# RS485.net
KiCad netlist of a schematic drawn in Altium Designer
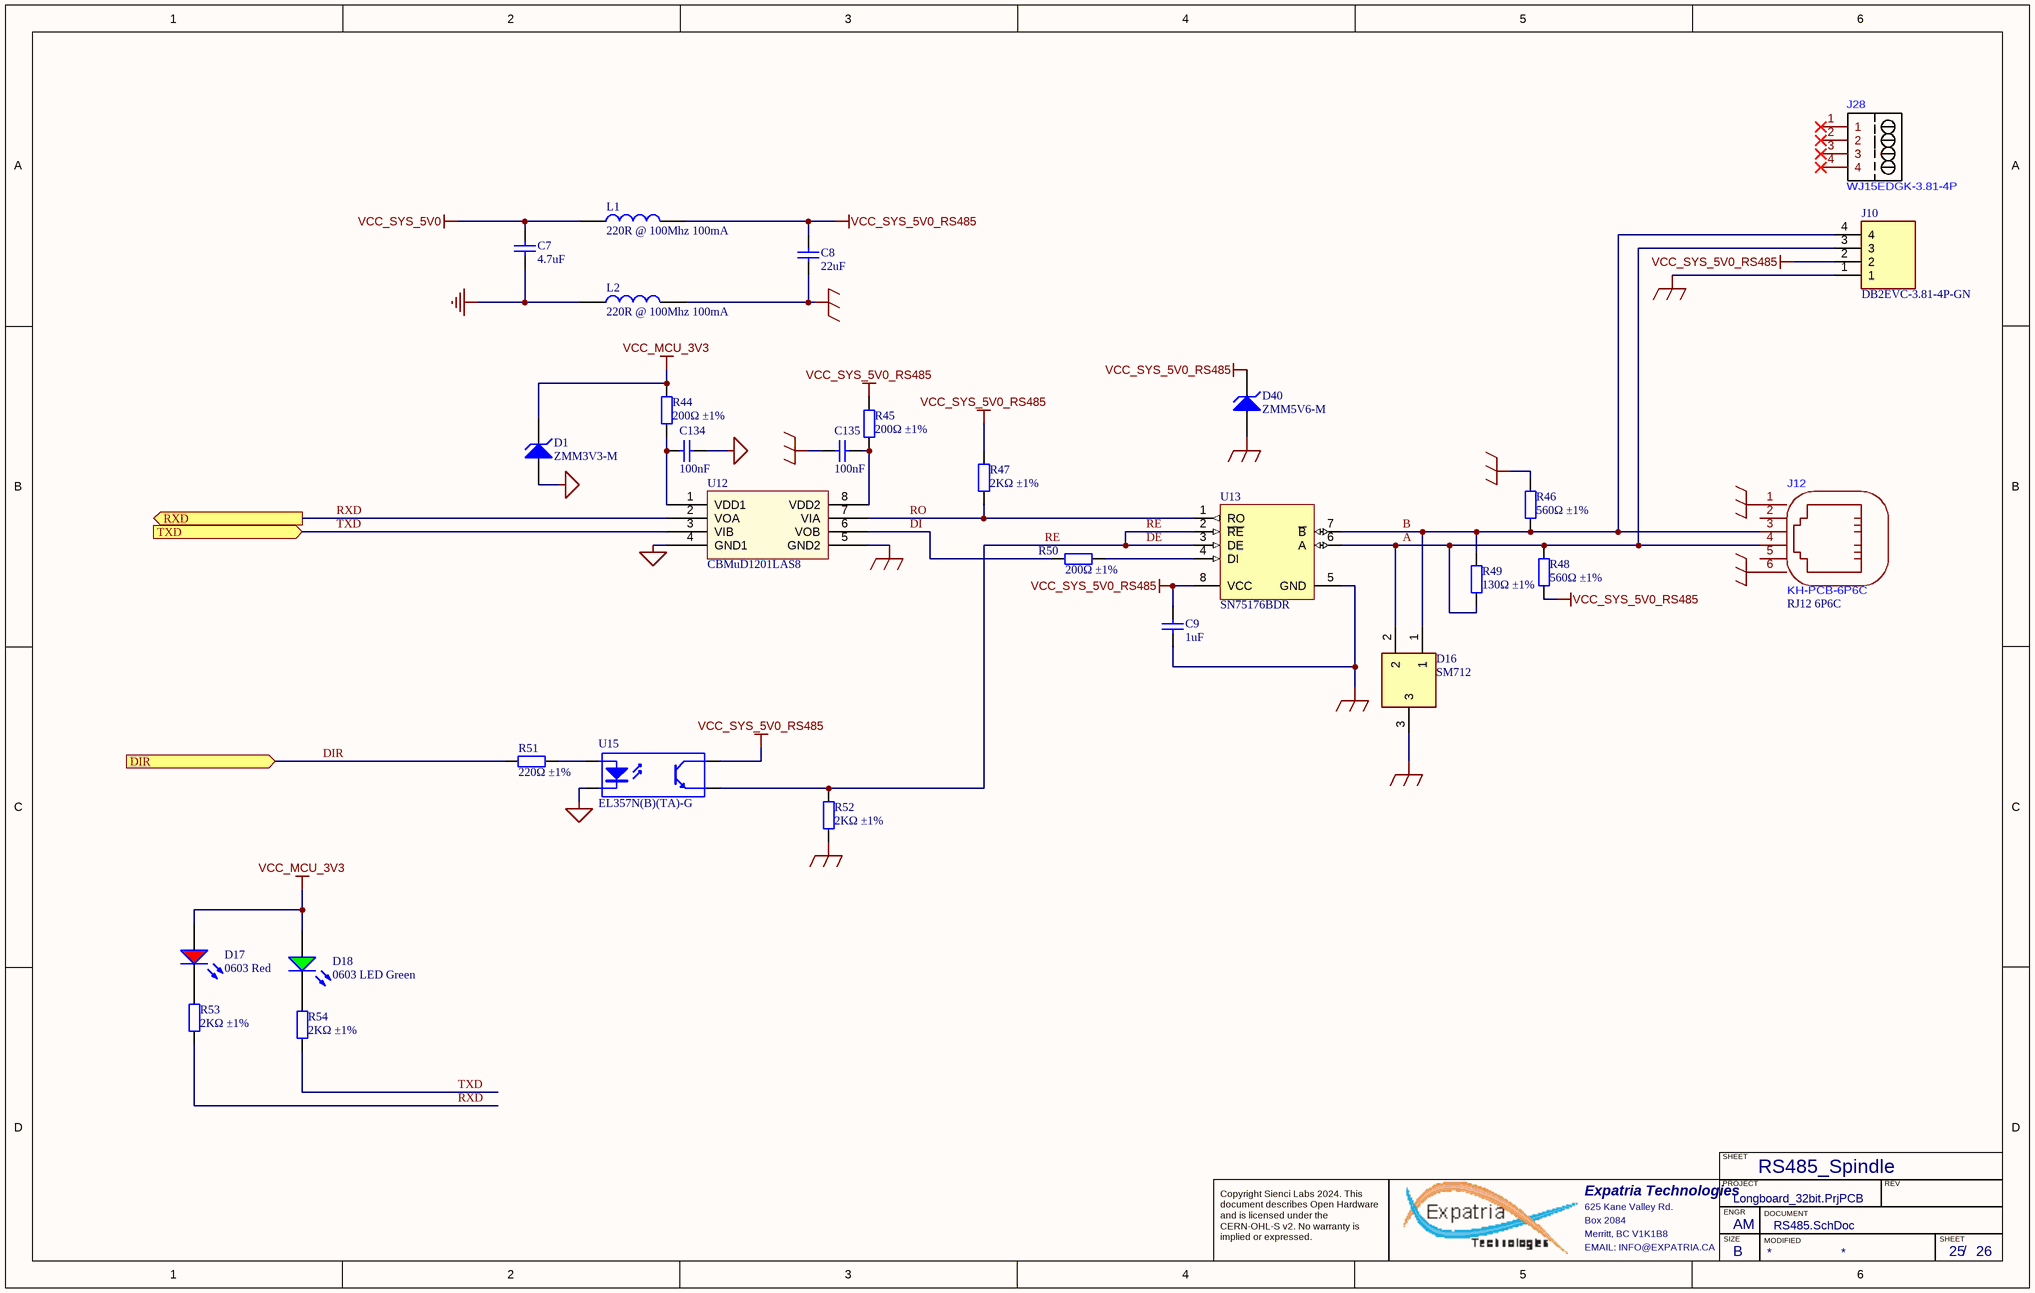
[diagram p0: RS485.SchDoc]

(export (version "E")
  (design (tool "Eeschema 10.0.6"))
  (components
    (comp (ref "C7")
      (value "4.7uF")
      (footprint "0805_C")
      (description "Chip capacitors")
      (fields
        (field (name "MANUFACTURER") "Samsung Electro-Mechanics")
        (field (name "MANUFACTURER PART NUMBER") "CL21A475KAQNNNE")
      )
      (libsource (lib "Cap") (part "0805 4.7uF (475) 10% 25V"))
    )
    (comp (ref "C8")
      (value "22uF")
      (footprint "0805_C")
      (description "25V 22uF X5R ±20% 0805 Multilayer Ceramic Capacitors MLCC - SMD/SMT ROHS")
      (fields (field (name "MANUFACTURER") "Samsung Electro-Mechanics") (field (name "TOLERANCE") "20%"))
      (libsource (lib "Sienci_Labs") (part "0805 22uF (226) 20% 25V"))
    )
    (comp (ref "C9")
      (value "1uF")
      (footprint "0603_C")
      (description "Chip capacitors")
      (fields
        (field (name "MANUFACTURER") "Samsung Electro-Mechanics")
        (field (name "MANUFACTURER PART NUMBER") "CL10A105KB8NNNC")
      )
      (libsource (lib "Cap") (part "0603 1uF (105) 10% 50V"))
    )
    (comp (ref "C134")
      (value "100nF")
      (footprint "0402_C")
      (description "16V 100nF X7R ±10% 0402 Multilayer Ceramic Capacitors MLCC - SMD/SMT ROHS")
      (fields (field (name "MANUFACTURER") "Samsung Electro-Mechanics") (field (name "TOLERANCE") "10%"))
      (libsource (lib "Sienci_Labs") (part "0402 100nF (104) 10% 16V"))
    )
    (comp (ref "C135")
      (value "100nF")
      (footprint "0402_C")
      (description "16V 100nF X7R ±10% 0402 Multilayer Ceramic Capacitors MLCC - SMD/SMT ROHS")
      (fields (field (name "MANUFACTURER") "Samsung Electro-Mechanics") (field (name "TOLERANCE") "10%"))
      (libsource (lib "Sienci_Labs") (part "0402 100nF (104) 10% 16V"))
    )
    (comp (ref "D1")
      (value "ZMM3V3-M")
      (footprint "LL-34")
      (description "Single 3.1V~3.5V 500mW 3.3V LL-34 Zener Diodes ROHS")
      (fields (field (name "MANUFACTURER") "ST(Semtech)"))
      (libsource (lib "Sienci_Labs") (part "LL-34 ZMM3V3-M"))
    )
    (comp (ref "D16")
      (value "SM712")
      (footprint "SOT95P230X117-3N")
      (description "Bidirectional 12V (Max), 7V (Max) 7.5V / 13.3V 10V / 20V 12A(8/20us) SOT-23-3 TVS RoHS")
      (fields (field (name "MANUFACTURER") "DOWO"))
      (libsource (lib "Sienci_Labs") (part "CDSOT23-SM712"))
    )
    (comp (ref "D17")
      (value "0603 Red")
      (footprint "0603_LED_S1")
      (fields
        (field (name "MANUFACTURER") "Everlight Elec")
        (field (name "MANUFACTURER PART NUMBER") "19-213SURC/S530-A3/TR8")
      )
      (libsource (lib "Sienci_Labs") (part "19-213SURC/S530-A3/TR8"))
    )
    (comp (ref "D18")
      (value "0603 LED Green")
      (footprint "0603_LED_S1 - GREEN")
      (fields
        (field (name "MANUFACTURER PART NUMBER") "19-217/GHC-YR1S2/3T")
        (field (name "MANUFACTURER") "Everlight Elec")
      )
      (libsource (lib "Sienci_Labs") (part "19-217/GHC-YR1S2/3T"))
    )
    (comp (ref "D40")
      (value "ZMM5V6-M")
      (footprint "LL-34")
      (description "Single 5.2V~6V 500mW 5.6V LL-34 Zener Diodes ROHS")
      (fields (field (name "MANUFACTURER") "ST(Semtech)"))
      (libsource (lib "Sienci_Labs") (part "LL-34 ZMM5V6-M"))
    )
    (comp (ref "J10")
      (value "DB2EVC-3.81-4P-GN")
      (footprint "CONN-TH_5P-P3.81_DB2EVC-3.81-4p")
      (description "3.81mm Green Board Edge/Receptacle-Close Push-Pull,P=3.81mm Pluggable System Terminal Block ROHS")
      (fields (field (name "MANUFACTURER") "DIBO"))
      (libsource (lib "Sienci_Labs") (part "DB2EVC-3.81-4P-GN"))
    )
    (comp (ref "J12")
      (value "KH-PCB-6P6C")
      (footprint "RJ11-TH_DS1133-S60BPX")
      (fields
        (field (name "MANUFACTURER") "Shenzhen Kinghelm Elec")
        (field (name "ALTIUM_VALUE") "RJ12 6P6C")
      )
      (libsource (lib "Sienci_Labs") (part "KH-PCB-6P6C"))
    )
    (comp (ref "J28")
      (value "WJ15EDGK-3.81-4P")
      (description "3.81mm Green Plug P=3.81mm Pluggable System Terminal Block ROHS")
      (fields (field (name "MANUFACTURER") "Ningbo"))
      (libsource (lib "Sienci_Labs") (part "WJ15EDGK-3.81-4P"))
    )
    (comp (ref "L1")
      (value "220R @ 100Mhz 100mA")
      (footprint "0402_L")
      (description "700mΩ ±25% 220Ω@100MHz 0402 Ferrite Beads ROHS")
      (fields
        (field (name "MANUFACTURER PART NUMBER") "CBG100505U221T")
        (field (name "MANUFACTURER") "FH (Guangdong Fenghua Advanced Tech)")
      )
      (libsource (lib "Sienci_Labs") (part "0402 220R@100Mhz 0.1A"))
    )
    (comp (ref "L2")
      (value "220R @ 100Mhz 100mA")
      (footprint "0402_L")
      (description "700mΩ ±25% 220Ω@100MHz 0402 Ferrite Beads ROHS")
      (fields
        (field (name "MANUFACTURER PART NUMBER") "CBG100505U221T")
        (field (name "MANUFACTURER") "FH (Guangdong Fenghua Advanced Tech)")
      )
      (libsource (lib "Sienci_Labs") (part "0402 220R@100Mhz 0.1A"))
    )
    (comp (ref "R44")
      (value "200Ω ±1%")
      (footprint "0402_R")
      (description "Chip resistor")
      (fields
        (field (name "MANUFACTURER") "Uniroyal Elec")
        (field (name "MANUFACTURER PART NUMBER") "0402WGF2000TCE")
      )
      (libsource (lib "RES") (part "0402 200R (2000) 1%"))
    )
    (comp (ref "R45")
      (value "200Ω ±1%")
      (footprint "0402_R")
      (description "Chip resistor")
      (fields
        (field (name "MANUFACTURER") "Uniroyal Elec")
        (field (name "MANUFACTURER PART NUMBER") "0402WGF2000TCE")
      )
      (libsource (lib "RES") (part "0402 200R (2000) 1%"))
    )
    (comp (ref "R46")
      (value "560Ω ±1%")
      (footprint "0603_R")
      (description "Chip resistor")
      (fields
        (field (name "MANUFACTURER") "Uniroyal Elec")
        (field (name "MANUFACTURER PART NUMBER") "0603WAF5600T5E")
      )
      (libsource (lib "RES") (part "0603 560R (5600) 1%"))
    )
    (comp (ref "R47")
      (value "2KΩ ±1%")
      (footprint "0603_R")
      (description "Chip resistor")
      (fields
        (field (name "MANUFACTURER") "Uniroyal Elec")
        (field (name "MANUFACTURER PART NUMBER") "0603WAF2001T5E")
      )
      (libsource (lib "RES") (part "0603 2K (2001) 1%"))
    )
    (comp (ref "R48")
      (value "560Ω ±1%")
      (footprint "0603_R")
      (description "Chip resistor")
      (fields
        (field (name "MANUFACTURER") "Uniroyal Elec")
        (field (name "MANUFACTURER PART NUMBER") "0603WAF5600T5E")
      )
      (libsource (lib "RES") (part "0603 560R (5600) 1%"))
    )
    (comp (ref "R49")
      (value "130Ω ±1%")
      (footprint "0603_R")
      (description "Chip resistor")
      (fields
        (field (name "MANUFACTURER") "Uniroyal Elec")
        (field (name "MANUFACTURER PART NUMBER") "0603WAF1300T5E")
      )
      (libsource (lib "RES") (part "0603 130R (1300) 1%"))
    )
    (comp (ref "R50")
      (value "200Ω ±1%")
      (footprint "0402_R")
      (description "Chip resistor")
      (fields
        (field (name "MANUFACTURER") "Uniroyal Elec")
        (field (name "MANUFACTURER PART NUMBER") "0402WGF2000TCE")
      )
      (libsource (lib "") (part "0402 200R (2000) 1%_1"))
    )
    (comp (ref "R51")
      (value "220Ω ±1%")
      (footprint "0402_R")
      (description "Chip resistor")
      (fields
        (field (name "MANUFACTURER") "Uniroyal Elec")
        (field (name "MANUFACTURER PART NUMBER") "0402WGF2200TCE")
      )
      (libsource (lib "RES") (part "0402 220R (2200) 1%"))
    )
    (comp (ref "R52")
      (value "2KΩ ±1%")
      (footprint "0603_R")
      (description "Chip resistor")
      (fields
        (field (name "MANUFACTURER") "Uniroyal Elec")
        (field (name "MANUFACTURER PART NUMBER") "0603WAF2001T5E")
      )
      (libsource (lib "RES") (part "0603 2K (2001) 1%"))
    )
    (comp (ref "R53")
      (value "2KΩ ±1%")
      (footprint "0603_R")
      (description "Chip resistor")
      (fields
        (field (name "MANUFACTURER") "Uniroyal Elec")
        (field (name "MANUFACTURER PART NUMBER") "0603WAF2001T5E")
      )
      (libsource (lib "RES") (part "0603 2K (2001) 1%"))
    )
    (comp (ref "R54")
      (value "2KΩ ±1%")
      (footprint "0603_R")
      (description "Chip resistor")
      (fields
        (field (name "MANUFACTURER") "Uniroyal Elec")
        (field (name "MANUFACTURER PART NUMBER") "0603WAF2001T5E")
      )
      (libsource (lib "RES") (part "0603 2K (2001) 1%"))
    )
    (comp (ref "U12")
      (value "CBMuD1201LAS8")
      (footprint "SOIC-8_150mil")
      (description "Dual Channel Isolator")
      (fields (field (name "MANUFACTURER") "Corebai Microelectronics"))
      (libsource (lib "Sienci_Labs") (part "CBMuD1201LAS8"))
    )
    (comp (ref "U13")
      (value "SN75176BDR")
      (footprint "SOIC-8_150mil")
      (description "RS-485/RS-422")
      (fields (field (name "MANUFACTURER") "Texas Instruments"))
      (libsource (lib "IC") (part "SN75176BDR_[C7063]"))
    )
    (comp (ref "U15")
      (value "EL357N(B)(TA)-G")
      (footprint "Miscellaneous Devices LC:SOP-4_P2.54")
      (description "80V 3750V 50mA 0.1V@1mA,20mA 1 6V 1.2V DC SOP-4-2.54mm Optocouplers - Phototransistor Output ROHS")
      (fields (field (name "MANUFACTURER") "Everlight Elec"))
      (libsource (lib "IC") (part "EL357N(B)(TA)-G_[C6649]"))
    )
  )
  (nets
    (net (code "1") (name "/A") (class "Default")
      (node (ref "D16") (pin "2") (pinfunction "2_2") (pintype "passive"))
      (node (ref "J10") (pin "3") (pinfunction "3_3") (pintype "passive"))
      (node (ref "J12") (pin "4") (pinfunction "PGD_4") (pintype "passive"))
      (node (ref "R48") (pin "1") (pinfunction "1_1") (pintype "passive"))
      (node (ref "R49") (pin "1") (pinfunction "1_1") (pintype "passive"))
      (node (ref "U13") (pin "6") (pinfunction "A_6") (pintype "bidirectional"))
    )
    (net (code "2") (name "/B") (class "Default")
      (node (ref "D16") (pin "1") (pinfunction "1_1") (pintype "passive"))
      (node (ref "J10") (pin "4") (pinfunction "4_4") (pintype "passive"))
      (node (ref "J12") (pin "3") (pinfunction "VSS_3") (pintype "passive"))
      (node (ref "R46") (pin "2") (pinfunction "2_2") (pintype "passive"))
      (node (ref "R49") (pin "2") (pinfunction "2_2") (pintype "passive"))
      (node (ref "U13") (pin "7") (pinfunction "~{B}_7") (pintype "bidirectional"))
    )
    (net (code "3") (name "/DE") (class "Default")
      (node (ref "R52") (pin "2") (pinfunction "2_2") (pintype "passive"))
      (node (ref "U13") (pin "2") (pinfunction "~{RE}_2") (pintype "input"))
      (node (ref "U13") (pin "3") (pinfunction "DE_3") (pintype "input"))
      (node (ref "U15") (pin "3") (pinfunction "E_3") (pintype "passive"))
    )
    (net (code "4") (name "/DI") (class "Default")
      (node (ref "R50") (pin "2") (pinfunction "2_2") (pintype "passive"))
      (node (ref "U12") (pin "6") (pinfunction "VOB_6") (pintype "passive"))
    )
    (net (code "5") (name "/DIR") (class "Default")
      (node (ref "R51") (pin "2") (pinfunction "2_2") (pintype "passive"))
    )
    (net (code "6") (name "/RO") (class "Default")
      (node (ref "R47") (pin "1") (pinfunction "1_1") (pintype "passive"))
      (node (ref "U12") (pin "7") (pinfunction "VIA_7") (pintype "passive"))
      (node (ref "U13") (pin "1") (pinfunction "RO_1") (pintype "output"))
    )
    (net (code "7") (name "/RXD") (class "Default")
      (node (ref "R53") (pin "1") (pinfunction "1_1") (pintype "passive"))
      (node (ref "U12") (pin "2") (pinfunction "VOA_2") (pintype "passive"))
    )
    (net (code "8") (name "/TXD") (class "Default")
      (node (ref "R54") (pin "1") (pinfunction "1_1") (pintype "passive"))
      (node (ref "U12") (pin "3") (pinfunction "VIB_3") (pintype "passive"))
    )
    (net (code "9") (name "GND") (class "Default")
      (node (ref "C7") (pin "1") (pinfunction "1_1") (pintype "passive"))
      (node (ref "L2") (pin "1") (pinfunction "1_1") (pintype "passive"))
    )
    (net (code "10") (name "MCU_GND") (class "Default")
      (node (ref "C134") (pin "2") (pinfunction "2_2") (pintype "passive"))
      (node (ref "D1") (pin "1") (pinfunction "A_1") (pintype "passive"))
      (node (ref "U12") (pin "4") (pinfunction "GND1_4") (pintype "passive"))
      (node (ref "U15") (pin "2") (pinfunction "K_2") (pintype "passive"))
    )
    (net (code "11") (name "MOD_GND") (class "Default")
      (node (ref "C135") (pin "1") (pinfunction "1_1") (pintype "passive"))
      (node (ref "C8") (pin "1") (pinfunction "1_1") (pintype "passive"))
      (node (ref "C9") (pin "1") (pinfunction "1_1") (pintype "passive"))
      (node (ref "D16") (pin "3") (pinfunction "3_3") (pintype "passive"))
      (node (ref "D40") (pin "1") (pinfunction "A_1") (pintype "passive"))
      (node (ref "J10") (pin "1") (pinfunction "1_1") (pintype "passive"))
      (node (ref "J12") (pin "1") (pinfunction "MCLR_1") (pintype "passive"))
      (node (ref "J12") (pin "6") (pinfunction "NC_6") (pintype "passive"))
      (node (ref "L2") (pin "2") (pinfunction "2_2") (pintype "passive"))
      (node (ref "R46") (pin "1") (pinfunction "1_1") (pintype "passive"))
      (node (ref "R52") (pin "1") (pinfunction "1_1") (pintype "passive"))
      (node (ref "U12") (pin "5") (pinfunction "GND2_5") (pintype "passive"))
      (node (ref "U13") (pin "5") (pinfunction "GND_5") (pintype "power_in"))
    )
    (net (code "12") (name "Net-(D17-PadK)") (class "Default")
      (node (ref "D17") (pin "K") (pinfunction "K_K") (pintype "passive"))
      (node (ref "R53") (pin "2") (pinfunction "2_2") (pintype "passive"))
    )
    (net (code "13") (name "Net-(D18-PadK)") (class "Default")
      (node (ref "D18") (pin "K") (pinfunction "K_K") (pintype "passive"))
      (node (ref "R54") (pin "2") (pinfunction "2_2") (pintype "passive"))
    )
    (net (code "14") (name "Net-(U12-VDD1)") (class "Default")
      (node (ref "C134") (pin "1") (pinfunction "1_1") (pintype "passive"))
      (node (ref "R44") (pin "1") (pinfunction "1_1") (pintype "passive"))
      (node (ref "U12") (pin "1") (pinfunction "VDD1_1") (pintype "passive"))
    )
    (net (code "15") (name "Net-(U12-VDD2)") (class "Default")
      (node (ref "C135") (pin "2") (pinfunction "2_2") (pintype "passive"))
      (node (ref "R45") (pin "1") (pinfunction "1_1") (pintype "passive"))
      (node (ref "U12") (pin "8") (pinfunction "VDD2_8") (pintype "passive"))
    )
    (net (code "16") (name "Net-(U13-DI)") (class "Default")
      (node (ref "R50") (pin "1") (pinfunction "1_1") (pintype "passive"))
      (node (ref "U13") (pin "4") (pinfunction "DI_4") (pintype "input"))
    )
    (net (code "17") (name "Net-(U15-A)") (class "Default")
      (node (ref "R51") (pin "1") (pinfunction "1_1") (pintype "passive"))
      (node (ref "U15") (pin "1") (pinfunction "A_1") (pintype "passive"))
    )
    (net (code "18") (name "VCC_MCU_3V3") (class "Default")
      (node (ref "D1") (pin "2") (pinfunction "K_2") (pintype "passive"))
      (node (ref "D17") (pin "A") (pinfunction "A_A") (pintype "passive"))
      (node (ref "D18") (pin "A") (pinfunction "A_A") (pintype "passive"))
      (node (ref "R44") (pin "2") (pinfunction "2_2") (pintype "passive"))
    )
    (net (code "19") (name "VCC_SYS_5V0") (class "Default")
      (node (ref "C7") (pin "2") (pinfunction "2_2") (pintype "passive"))
      (node (ref "L1") (pin "1") (pinfunction "1_1") (pintype "passive"))
    )
    (net (code "20") (name "VCC_SYS_5V0_RS485") (class "Default")
      (node (ref "C8") (pin "2") (pinfunction "2_2") (pintype "passive"))
      (node (ref "C9") (pin "2") (pinfunction "2_2") (pintype "passive"))
      (node (ref "D40") (pin "2") (pinfunction "K_2") (pintype "passive"))
      (node (ref "J10") (pin "2") (pinfunction "2_2") (pintype "passive"))
      (node (ref "L1") (pin "2") (pinfunction "2_2") (pintype "passive"))
      (node (ref "R45") (pin "2") (pinfunction "2_2") (pintype "passive"))
      (node (ref "R47") (pin "2") (pinfunction "2_2") (pintype "passive"))
      (node (ref "R48") (pin "2") (pinfunction "2_2") (pintype "passive"))
      (node (ref "U13") (pin "8") (pinfunction "VCC_8") (pintype "power_in"))
      (node (ref "U15") (pin "4") (pinfunction "C_4") (pintype "passive"))
    )
    (net (code "21") (name "unconnected-(J12-PGC-Pad5)") (class "Default")
      (node (ref "J12") (pin "5") (pinfunction "PGC_5") (pintype "passive"))
    )
    (net (code "22") (name "unconnected-(J12-VDD-Pad2)") (class "Default")
      (node (ref "J12") (pin "2") (pinfunction "VDD_2") (pintype "passive"))
    )
    (net (code "23") (name "unconnected-(J28-Pad1)") (class "Default")
      (node (ref "J28") (pin "1") (pinfunction "1_1") (pintype "passive+no_connect"))
    )
    (net (code "24") (name "unconnected-(J28-Pad2)") (class "Default")
      (node (ref "J28") (pin "2") (pinfunction "2_2") (pintype "passive+no_connect"))
    )
    (net (code "25") (name "unconnected-(J28-Pad3)") (class "Default")
      (node (ref "J28") (pin "3") (pinfunction "3_3") (pintype "passive+no_connect"))
    )
    (net (code "26") (name "unconnected-(J28-Pad4)") (class "Default")
      (node (ref "J28") (pin "4") (pinfunction "4_4") (pintype "passive+no_connect"))
    )
  )
)
